# Power_Supply_5V.net
KiCad netlist of a schematic drawn in EAGLE
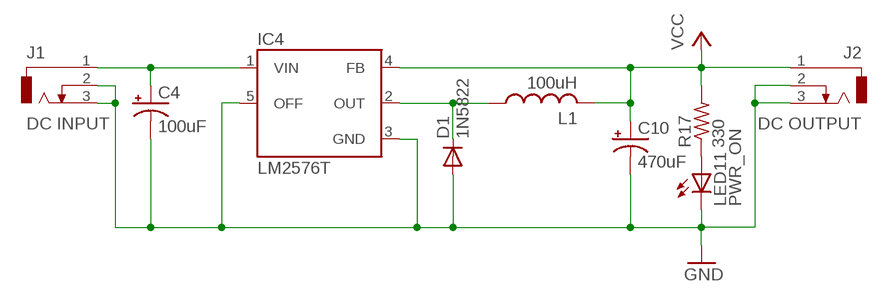
[diagram p0: schematic, sheet 1]

(export (version "E")
  (design (tool "Eeschema 10.0.6"))
  (components
    (comp (ref "C4")
      (value "100uF")
      (footprint "eagle-import:E2,5-6")
      (libsource (lib "eagle-import") (part "CPOL-USE2.5-6"))
    )
    (comp (ref "C10")
      (value "470uF")
      (footprint "eagle-import:E3,5-8")
      (libsource (lib "eagle-import") (part "CPOL-USE3.5-8"))
    )
    (comp (ref "D1")
      (value "1N5822")
      (footprint "eagle-import:DO201-15")
      (libsource (lib "eagle-import") (part "1N5400"))
    )
    (comp (ref "IC4")
      (value "LM2576T")
      (footprint "eagle-import:TO220-5")
      (libsource (lib "eagle-import") (part "LM2576T"))
    )
    (comp (ref "J1")
      (value "DC INPUT")
      (footprint "eagle-import:DCJ0202")
      (libsource (lib "eagle-import") (part "DCJ0202"))
    )
    (comp (ref "J2")
      (value "DC OUTPUT")
      (footprint "eagle-import:DCJ0202")
      (libsource (lib "eagle-import") (part "DCJ0202"))
    )
    (comp (ref "L1")
      (value "100uH")
      (footprint "eagle-import:TJ3-U2")
      (libsource (lib "eagle-import") (part "L-USTJ3-U2"))
    )
    (comp (ref "LED11")
      (value "PWR_ON")
      (footprint "eagle-import:LED3MM")
      (libsource (lib "eagle-import") (part "LED3MM"))
    )
    (comp (ref "R17")
      (value "330")
      (footprint "eagle-import:0207_10")
      (libsource (lib "eagle-import") (part "R-US_0207/10"))
    )
  )
  (nets
    (net (code "1") (name "GND") (class "Default")
      (node (ref "C10") (pin "-") (pinfunction "-_-") (pintype "passive"))
      (node (ref "C4") (pin "-") (pinfunction "-_-") (pintype "passive"))
      (node (ref "D1") (pin "A") (pinfunction "A_A") (pintype "passive"))
      (node (ref "IC4") (pin "3") (pinfunction "GND_3") (pintype "power_in"))
      (node (ref "IC4") (pin "5") (pinfunction "OFF_5") (pintype "input"))
      (node (ref "J1") (pin "2") (pinfunction "2_2") (pintype "passive"))
      (node (ref "J1") (pin "3") (pinfunction "3_3") (pintype "passive"))
      (node (ref "J2") (pin "2") (pinfunction "2_2") (pintype "passive"))
      (node (ref "J2") (pin "3") (pinfunction "3_3") (pintype "passive"))
      (node (ref "LED11") (pin "K") (pinfunction "C_K") (pintype "passive"))
    )
    (net (code "2") (name "Net-(IC4-OUT)") (class "Default")
      (node (ref "D1") (pin "C") (pinfunction "C_C") (pintype "passive"))
      (node (ref "IC4") (pin "2") (pinfunction "OUT_2") (pintype "output"))
      (node (ref "L1") (pin "1") (pinfunction "1_1") (pintype "passive"))
    )
    (net (code "3") (name "Net-(IC4-VIN)") (class "Default")
      (node (ref "C4") (pin "+") (pinfunction "+_+") (pintype "passive"))
      (node (ref "IC4") (pin "1") (pinfunction "VIN_1") (pintype "power_in"))
      (node (ref "J1") (pin "1") (pinfunction "1_1") (pintype "passive"))
    )
    (net (code "4") (name "Net-(LED11-PadA)") (class "Default")
      (node (ref "LED11") (pin "A") (pinfunction "A_A") (pintype "passive"))
      (node (ref "R17") (pin "1") (pinfunction "1_1") (pintype "passive"))
    )
    (net (code "5") (name "VCC") (class "Default")
      (node (ref "C10") (pin "+") (pinfunction "+_+") (pintype "passive"))
      (node (ref "IC4") (pin "4") (pinfunction "FB_4") (pintype "input"))
      (node (ref "J2") (pin "1") (pinfunction "1_1") (pintype "passive"))
      (node (ref "L1") (pin "2") (pinfunction "2_2") (pintype "passive"))
      (node (ref "R17") (pin "2") (pinfunction "2_2") (pintype "passive"))
    )
  )
)
